# ftdi_programmer_to_atmega_328p.net
KiCad netlist of a schematic drawn in EAGLE
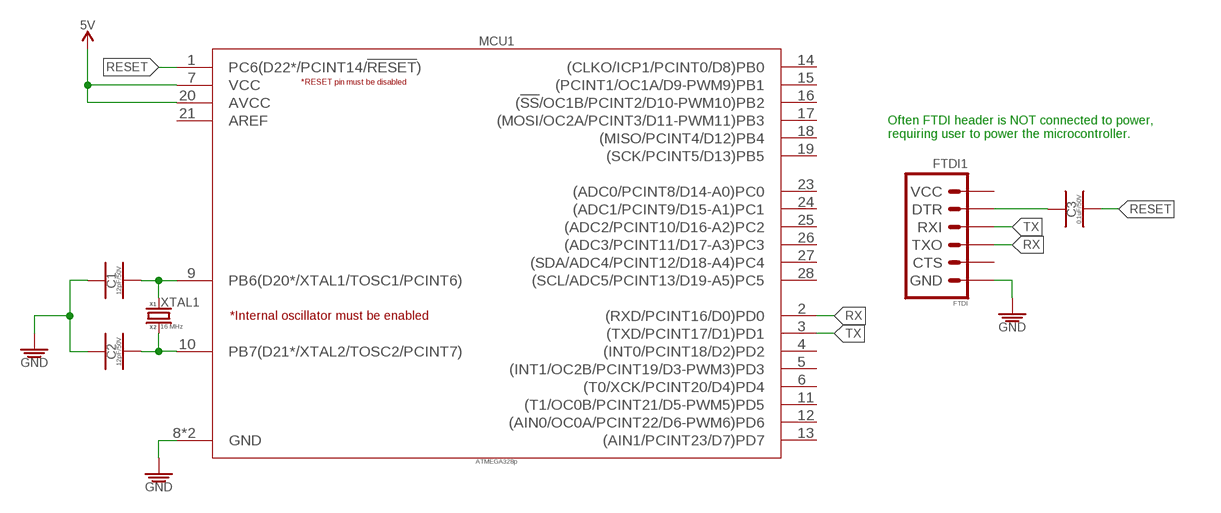
[diagram p0: schematic, sheet 1]

(export (version "E")
  (design (tool "Eeschema 10.0.6"))
  (components
    (comp (ref "C1")
      (value "12pF/50V")
      (footprint "eagle-import:_CER_PTH_LS2.5_L4-W2.5-H5.58")
      (fields (field (name "MFR") "Vishay BC Components") (field (name "MPN") "K120J15C0GF5TL2"))
      (libsource (lib "eagle-import") (part "12PF_PTH-CER_50V-5%"))
    )
    (comp (ref "C2")
      (value "12pF/50V")
      (footprint "eagle-import:_CER_PTH_LS2.5_L4-W2.5-H5.58")
      (fields (field (name "MFR") "Vishay BC Components") (field (name "MPN") "K120J15C0GF5TL2"))
      (libsource (lib "eagle-import") (part "12PF_PTH-CER_50V-5%"))
    )
    (comp (ref "C3")
      (value "0.1uF/50V")
      (footprint "eagle-import:_CER_PTH_LS2.5_L4-W2.5-H5.58")
      (fields (field (name "MFR") "Vishay BC Components") (field (name "MPN") "K104K15X7RF5TL2"))
      (libsource (lib "eagle-import") (part "0.1UF_PTH-CER_50V-10%"))
    )
    (comp (ref "FTDI1")
      (value "FTDI")
      (footprint "eagle-import:HDRV6W64P254_1X6_1524X254X838B_FTDI")
      (fields (field (name "MFR") "SparkFun Electronics") (field (name "MPN") "DEV-09873"))
      (libsource (lib "eagle-import") (part "FTDI_PTH_VERT_MALE_2.54MM"))
    )
    (comp (ref "MCU1")
      (value "ATMEGA328p")
      (footprint "eagle-import:DIP762W53P254L3467H472Q28B")
      (fields (field (name "MFR") "Microchip Technology") (field (name "MPN") "ATMEGA328P-PU"))
      (libsource (lib "eagle-import") (part "ATMEGA328P-28_28-PDIP_8BIT_32KB"))
    )
    (comp (ref "XTAL1")
      (value "16 MHz")
      (footprint "eagle-import:HC-49_US")
      (fields (field (name "MFR") "Abracon LLC") (field (name "MPN") "ABL-16.000MHZ-B2"))
      (libsource (lib "eagle-import") (part "CRYSTAL_ABL_16MHZ_18PF"))
    )
  )
  (nets
    (net (code "1") (name "5V") (class "Default")
      (node (ref "MCU1") (pin "20") (pinfunction "AVCC_20") (pintype "power_in"))
      (node (ref "MCU1") (pin "7") (pinfunction "VCC_7") (pintype "power_in"))
    )
    (net (code "2") (name "GND") (class "Default")
      (node (ref "C1") (pin "P$1") (pinfunction "1_P$1") (pintype "passive"))
      (node (ref "C2") (pin "P$1") (pinfunction "1_P$1") (pintype "passive"))
      (node (ref "FTDI1") (pin "GND") (pinfunction "GND_GND") (pintype "power_in"))
      (node (ref "MCU1") (pin "22") (pinfunction "GND_22") (pintype "power_in"))
      (node (ref "MCU1") (pin "8") (pinfunction "GND_8") (pintype "power_in"))
    )
    (net (code "3") (name "Net-(C1-2)") (class "Default")
      (node (ref "C1") (pin "P$2") (pinfunction "2_P$2") (pintype "passive"))
      (node (ref "MCU1") (pin "9") (pinfunction "PB6(D20*/XTAL1/TOSC1/PCINT6)_9") (pintype "bidirectional"))
      (node (ref "XTAL1") (pin "P$1") (pinfunction "XTAL1_P$1") (pintype "passive"))
    )
    (net (code "4") (name "Net-(C2-2)") (class "Default")
      (node (ref "C2") (pin "P$2") (pinfunction "2_P$2") (pintype "passive"))
      (node (ref "MCU1") (pin "10") (pinfunction "PB7(D21*/XTAL2/TOSC2/PCINT7)_10") (pintype "bidirectional"))
      (node (ref "XTAL1") (pin "P$2") (pinfunction "XTAL2_P$2") (pintype "passive"))
    )
    (net (code "5") (name "Net-(C3-1)") (class "Default")
      (node (ref "C3") (pin "P$1") (pinfunction "1_P$1") (pintype "passive"))
      (node (ref "FTDI1") (pin "DTR") (pinfunction "DTR_DTR") (pintype "bidirectional"))
    )
    (net (code "6") (name "RESET") (class "Default")
      (node (ref "C3") (pin "P$2") (pinfunction "2_P$2") (pintype "passive"))
      (node (ref "MCU1") (pin "1") (pinfunction "PC6(D22*/PCINT14/~{RESET})_1") (pintype "bidirectional"))
    )
    (net (code "7") (name "RX") (class "Default")
      (node (ref "FTDI1") (pin "TX") (pinfunction "TXO_TX") (pintype "output"))
      (node (ref "MCU1") (pin "2") (pinfunction "(RXD/PCINT16/D0)PD0_2") (pintype "bidirectional"))
    )
    (net (code "8") (name "TX") (class "Default")
      (node (ref "FTDI1") (pin "RX") (pinfunction "RXI_RX") (pintype "input"))
      (node (ref "MCU1") (pin "3") (pinfunction "(TXD/PCINT17/D1)PD1_3") (pintype "bidirectional"))
    )
    (net (code "9") (name "unconnected-(FTDI1-PadCTS)") (class "Default")
      (node (ref "FTDI1") (pin "CTS") (pinfunction "CTS_CTS") (pintype "bidirectional"))
    )
    (net (code "10") (name "unconnected-(FTDI1-PadVCC)") (class "Default")
      (node (ref "FTDI1") (pin "VCC") (pinfunction "VCC_VCC") (pintype "no_connect"))
    )
    (net (code "11") (name "unconnected-(MCU1-(ADC0{slash}PCINT8{slash}D14-A0)PC0-Pad23)") (class "Default")
      (node (ref "MCU1") (pin "23") (pinfunction "(ADC0/PCINT8/D14-A0)PC0_23") (pintype "bidirectional"))
    )
    (net (code "12") (name "unconnected-(MCU1-(ADC1{slash}PCINT9{slash}D15-A1)PC1-Pad24)") (class "Default")
      (node (ref "MCU1") (pin "24") (pinfunction "(ADC1/PCINT9/D15-A1)PC1_24") (pintype "bidirectional"))
    )
    (net (code "13") (name "unconnected-(MCU1-(ADC2{slash}PCINT10{slash}D16-A2)PC2-Pad25)") (class "Default")
      (node (ref "MCU1") (pin "25") (pinfunction "(ADC2/PCINT10/D16-A2)PC2_25") (pintype "bidirectional"))
    )
    (net (code "14") (name "unconnected-(MCU1-(ADC3{slash}PCINT11{slash}D17-A3)PC3-Pad26)") (class "Default")
      (node (ref "MCU1") (pin "26") (pinfunction "(ADC3/PCINT11/D17-A3)PC3_26") (pintype "bidirectional"))
    )
    (net (code "15") (name "unconnected-(MCU1-(AIN0{slash}OC0A{slash}PCINT22{slash}D6-PWM6)PD6-Pad12)") (class "Default")
      (node (ref "MCU1") (pin "12") (pinfunction "(AIN0/OC0A/PCINT22/D6-PWM6)PD6_12") (pintype "bidirectional"))
    )
    (net (code "16") (name "unconnected-(MCU1-(AIN1{slash}PCINT23{slash}D7)PD7-Pad13)") (class "Default")
      (node (ref "MCU1") (pin "13") (pinfunction "(AIN1/PCINT23/D7)PD7_13") (pintype "bidirectional"))
    )
    (net (code "17") (name "unconnected-(MCU1-(CLKO{slash}ICP1{slash}PCINT0{slash}D8)PB0-Pad14)") (class "Default")
      (node (ref "MCU1") (pin "14") (pinfunction "(CLKO/ICP1/PCINT0/D8)PB0_14") (pintype "bidirectional"))
    )
    (net (code "18") (name "unconnected-(MCU1-(INT0{slash}PCINT18{slash}D2)PD2-Pad4)") (class "Default")
      (node (ref "MCU1") (pin "4") (pinfunction "(INT0/PCINT18/D2)PD2_4") (pintype "bidirectional"))
    )
    (net (code "19") (name "unconnected-(MCU1-(INT1{slash}OC2B{slash}PCINT19{slash}D3-PWM3)PD3-Pad5)") (class "Default")
      (node (ref "MCU1") (pin "5") (pinfunction "(INT1/OC2B/PCINT19/D3-PWM3)PD3_5") (pintype "bidirectional"))
    )
    (net (code "20") (name "unconnected-(MCU1-(MISO{slash}PCINT4{slash}D12)PB4-Pad18)") (class "Default")
      (node (ref "MCU1") (pin "18") (pinfunction "(MISO/PCINT4/D12)PB4_18") (pintype "bidirectional"))
    )
    (net (code "21") (name "unconnected-(MCU1-(MOSI{slash}OC2A{slash}PCINT3{slash}D11-PWM11)PB3-Pad17)") (class "Default")
      (node (ref "MCU1") (pin "17") (pinfunction "(MOSI/OC2A/PCINT3/D11-PWM11)PB3_17") (pintype "bidirectional"))
    )
    (net (code "22") (name "unconnected-(MCU1-(PCINT1{slash}OC1A{slash}D9-PWM9)PB1-Pad15)") (class "Default")
      (node (ref "MCU1") (pin "15") (pinfunction "(PCINT1/OC1A/D9-PWM9)PB1_15") (pintype "bidirectional"))
    )
    (net (code "23") (name "unconnected-(MCU1-(SCK{slash}PCINT5{slash}D13)PB5-Pad19)") (class "Default")
      (node (ref "MCU1") (pin "19") (pinfunction "(SCK/PCINT5/D13)PB5_19") (pintype "bidirectional"))
    )
    (net (code "24") (name "unconnected-(MCU1-(SCL{slash}ADC5{slash}PCINT13{slash}D19-A5)PC5-Pad28)") (class "Default")
      (node (ref "MCU1") (pin "28") (pinfunction "(SCL/ADC5/PCINT13/D19-A5)PC5_28") (pintype "bidirectional"))
    )
    (net (code "25") (name "unconnected-(MCU1-(SDA{slash}ADC4{slash}PCINT12{slash}D18-A4)PC4-Pad27)") (class "Default")
      (node (ref "MCU1") (pin "27") (pinfunction "(SDA/ADC4/PCINT12/D18-A4)PC4_27") (pintype "bidirectional"))
    )
    (net (code "26") (name "unconnected-(MCU1-(T0{slash}XCK{slash}PCINT20{slash}D4)PD4-Pad6)") (class "Default")
      (node (ref "MCU1") (pin "6") (pinfunction "(T0/XCK/PCINT20/D4)PD4_6") (pintype "bidirectional"))
    )
    (net (code "27") (name "unconnected-(MCU1-(T1{slash}OC0B{slash}PCINT21{slash}D5-PWM5)PD5-Pad11)") (class "Default")
      (node (ref "MCU1") (pin "11") (pinfunction "(T1/OC0B/PCINT21/D5-PWM5)PD5_11") (pintype "bidirectional"))
    )
    (net (code "28") (name "unconnected-(MCU1-(~{SS}{slash}OC1B{slash}PCINT2{slash}D10-PWM10)PB2-Pad16)") (class "Default")
      (node (ref "MCU1") (pin "16") (pinfunction "(~{SS}/OC1B/PCINT2/D10-PWM10)PB2_16") (pintype "bidirectional"))
    )
    (net (code "29") (name "unconnected-(MCU1-AREF-Pad21)") (class "Default")
      (node (ref "MCU1") (pin "21") (pinfunction "AREF_21") (pintype "passive"))
    )
  )
)
